# reg_smd_v-1-0.net
KiCad netlist of a schematic drawn in EAGLE
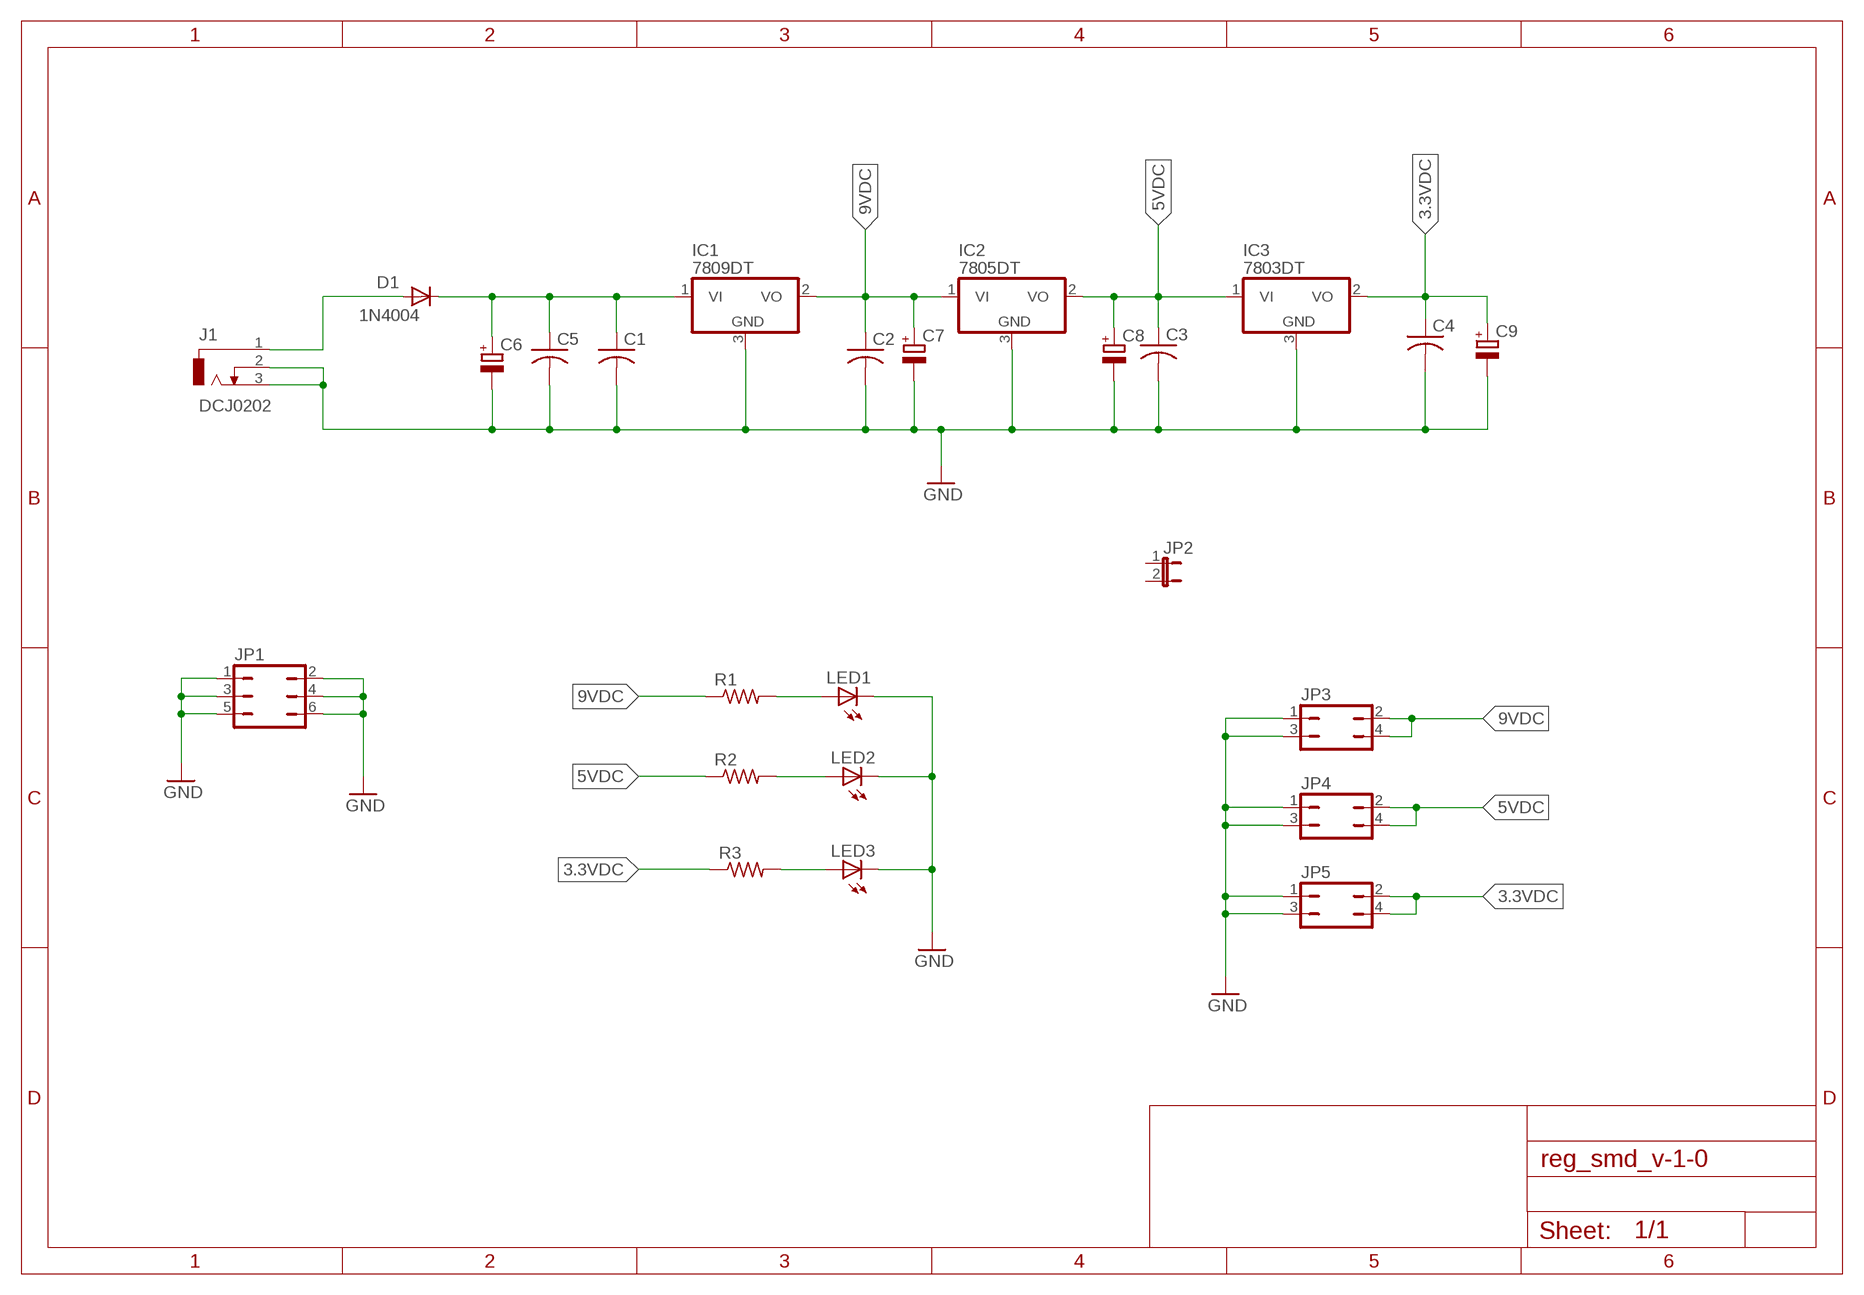
[diagram p0: schematic, sheet 1]

(export (version "E")
  (design (tool "Eeschema 10.0.6"))
  (components
    (comp (ref "C1")
      (value "C-USC1206")
      (footprint "eagle-import:C1206")
      (libsource (lib "eagle-import") (part "C-USC1206"))
    )
    (comp (ref "C2")
      (value "C-USC1206")
      (footprint "eagle-import:C1206")
      (libsource (lib "eagle-import") (part "C-USC1206"))
    )
    (comp (ref "C3")
      (value "C-USC1206")
      (footprint "eagle-import:C1206")
      (libsource (lib "eagle-import") (part "C-USC1206"))
    )
    (comp (ref "C4")
      (value "C-USC1206")
      (footprint "eagle-import:C1206")
      (libsource (lib "eagle-import") (part "C-USC1206"))
    )
    (comp (ref "C5")
      (value "C-USC1206")
      (footprint "eagle-import:C1206")
      (libsource (lib "eagle-import") (part "C-USC1206"))
    )
    (comp (ref "C6")
      (value "CPOL-EUE2.5-6")
      (footprint "eagle-import:E2,5-6")
      (libsource (lib "eagle-import") (part "CPOL-EUE2.5-6"))
    )
    (comp (ref "C7")
      (value "CPOL-EUE2.5-6")
      (footprint "eagle-import:E2,5-6")
      (libsource (lib "eagle-import") (part "CPOL-EUE2.5-6"))
    )
    (comp (ref "C8")
      (value "CPOL-EUE2.5-6")
      (footprint "eagle-import:E2,5-6")
      (libsource (lib "eagle-import") (part "CPOL-EUE2.5-6"))
    )
    (comp (ref "C9")
      (value "CPOL-EUE2.5-6")
      (footprint "eagle-import:E2,5-6")
      (libsource (lib "eagle-import") (part "CPOL-EUE2.5-6"))
    )
    (comp (ref "D1")
      (value "1N4004")
      (footprint "eagle-import:DO41-10")
      (libsource (lib "eagle-import") (part "1N4004"))
    )
    (comp (ref "IC1")
      (value "7809DT")
      (footprint "eagle-import:TO252")
      (libsource (lib "eagle-import") (part "78DT06"))
    )
    (comp (ref "IC2")
      (value "7805DT")
      (footprint "eagle-import:TO252")
      (libsource (lib "eagle-import") (part "78DT06"))
    )
    (comp (ref "IC3")
      (value "7803DT")
      (footprint "eagle-import:TO252")
      (libsource (lib "eagle-import") (part "78DT06"))
    )
    (comp (ref "J1")
      (value "DCJ0202")
      (footprint "eagle-import:DCJ0202")
      (libsource (lib "eagle-import") (part "DCJ0202"))
    )
    (comp (ref "JP1")
      (value "JP3Q")
      (footprint "eagle-import:JP3Q")
      (libsource (lib "eagle-import") (part "JP3Q"))
    )
    (comp (ref "JP2")
      (value "JP1E")
      (footprint "eagle-import:JP1")
      (libsource (lib "eagle-import") (part "JP1E"))
    )
    (comp (ref "JP3")
      (value "JP2Q")
      (footprint "eagle-import:JP2Q")
      (libsource (lib "eagle-import") (part "JP2Q"))
    )
    (comp (ref "JP4")
      (value "JP2Q")
      (footprint "eagle-import:JP2Q")
      (libsource (lib "eagle-import") (part "JP2Q"))
    )
    (comp (ref "JP5")
      (value "JP2Q")
      (footprint "eagle-import:JP2Q")
      (libsource (lib "eagle-import") (part "JP2Q"))
    )
    (comp (ref "LED1")
      (value "LEDCHIPLED_1206")
      (footprint "eagle-import:CHIPLED_1206")
      (libsource (lib "eagle-import") (part "LEDCHIPLED_1206"))
    )
    (comp (ref "LED2")
      (value "LEDCHIPLED_1206")
      (footprint "eagle-import:CHIPLED_1206")
      (libsource (lib "eagle-import") (part "LEDCHIPLED_1206"))
    )
    (comp (ref "LED3")
      (value "LEDCHIPLED_1206")
      (footprint "eagle-import:CHIPLED_1206")
      (libsource (lib "eagle-import") (part "LEDCHIPLED_1206"))
    )
    (comp (ref "R1")
      (value "R-US_M1206")
      (footprint "eagle-import:M1206")
      (libsource (lib "eagle-import") (part "R-US_M1206"))
    )
    (comp (ref "R2")
      (value "R-US_M1206")
      (footprint "eagle-import:M1206")
      (libsource (lib "eagle-import") (part "R-US_M1206"))
    )
    (comp (ref "R3")
      (value "R-US_M1206")
      (footprint "eagle-import:M1206")
      (libsource (lib "eagle-import") (part "R-US_M1206"))
    )
  )
  (nets
    (net (code "1") (name "3.3VDC") (class "Default")
      (node (ref "C4") (pin "1") (pinfunction "1_1") (pintype "passive"))
      (node (ref "C9") (pin "+") (pinfunction "+_+") (pintype "passive"))
      (node (ref "IC3") (pin "2") (pinfunction "VO_2") (pintype "passive"))
      (node (ref "JP5") (pin "2") (pinfunction "2_2") (pintype "passive"))
      (node (ref "JP5") (pin "4") (pinfunction "4_4") (pintype "passive"))
      (node (ref "R3") (pin "1") (pinfunction "1_1") (pintype "passive"))
    )
    (net (code "2") (name "5VDC") (class "Default")
      (node (ref "C3") (pin "1") (pinfunction "1_1") (pintype "passive"))
      (node (ref "C8") (pin "+") (pinfunction "+_+") (pintype "passive"))
      (node (ref "IC2") (pin "2") (pinfunction "VO_2") (pintype "passive"))
      (node (ref "IC3") (pin "1") (pinfunction "VI_1") (pintype "input"))
      (node (ref "JP4") (pin "2") (pinfunction "2_2") (pintype "passive"))
      (node (ref "JP4") (pin "4") (pinfunction "4_4") (pintype "passive"))
      (node (ref "R2") (pin "1") (pinfunction "1_1") (pintype "passive"))
    )
    (net (code "3") (name "9VDC") (class "Default")
      (node (ref "C2") (pin "1") (pinfunction "1_1") (pintype "passive"))
      (node (ref "C7") (pin "+") (pinfunction "+_+") (pintype "passive"))
      (node (ref "IC1") (pin "2") (pinfunction "VO_2") (pintype "passive"))
      (node (ref "IC2") (pin "1") (pinfunction "VI_1") (pintype "input"))
      (node (ref "JP3") (pin "2") (pinfunction "2_2") (pintype "passive"))
      (node (ref "JP3") (pin "4") (pinfunction "4_4") (pintype "passive"))
      (node (ref "R1") (pin "1") (pinfunction "1_1") (pintype "passive"))
    )
    (net (code "4") (name "GND") (class "Default")
      (node (ref "C1") (pin "2") (pinfunction "2_2") (pintype "passive"))
      (node (ref "C2") (pin "2") (pinfunction "2_2") (pintype "passive"))
      (node (ref "C3") (pin "2") (pinfunction "2_2") (pintype "passive"))
      (node (ref "C4") (pin "2") (pinfunction "2_2") (pintype "passive"))
      (node (ref "C5") (pin "2") (pinfunction "2_2") (pintype "passive"))
      (node (ref "C6") (pin "-") (pinfunction "-_-") (pintype "passive"))
      (node (ref "C7") (pin "-") (pinfunction "-_-") (pintype "passive"))
      (node (ref "C8") (pin "-") (pinfunction "-_-") (pintype "passive"))
      (node (ref "C9") (pin "-") (pinfunction "-_-") (pintype "passive"))
      (node (ref "IC1") (pin "3") (pinfunction "GND_3") (pintype "passive"))
      (node (ref "IC2") (pin "3") (pinfunction "GND_3") (pintype "passive"))
      (node (ref "IC3") (pin "3") (pinfunction "GND_3") (pintype "passive"))
      (node (ref "J1") (pin "2") (pinfunction "2_2") (pintype "passive"))
      (node (ref "J1") (pin "3") (pinfunction "3_3") (pintype "passive"))
      (node (ref "JP1") (pin "1") (pinfunction "1_1") (pintype "passive"))
      (node (ref "JP1") (pin "2") (pinfunction "2_2") (pintype "passive"))
      (node (ref "JP1") (pin "3") (pinfunction "3_3") (pintype "passive"))
      (node (ref "JP1") (pin "4") (pinfunction "4_4") (pintype "passive"))
      (node (ref "JP1") (pin "5") (pinfunction "5_5") (pintype "passive"))
      (node (ref "JP1") (pin "6") (pinfunction "6_6") (pintype "passive"))
      (node (ref "JP3") (pin "1") (pinfunction "1_1") (pintype "passive"))
      (node (ref "JP3") (pin "3") (pinfunction "3_3") (pintype "passive"))
      (node (ref "JP4") (pin "1") (pinfunction "1_1") (pintype "passive"))
      (node (ref "JP4") (pin "3") (pinfunction "3_3") (pintype "passive"))
      (node (ref "JP5") (pin "1") (pinfunction "1_1") (pintype "passive"))
      (node (ref "JP5") (pin "3") (pinfunction "3_3") (pintype "passive"))
      (node (ref "LED1") (pin "C") (pinfunction "C_C") (pintype "passive"))
      (node (ref "LED2") (pin "C") (pinfunction "C_C") (pintype "passive"))
      (node (ref "LED3") (pin "C") (pinfunction "C_C") (pintype "passive"))
    )
    (net (code "5") (name "Net-(D1-PadA)") (class "Default")
      (node (ref "D1") (pin "A") (pinfunction "A_A") (pintype "passive"))
      (node (ref "J1") (pin "1") (pinfunction "1_1") (pintype "passive"))
    )
    (net (code "6") (name "Net-(IC1-VI)") (class "Default")
      (node (ref "C1") (pin "1") (pinfunction "1_1") (pintype "passive"))
      (node (ref "C5") (pin "1") (pinfunction "1_1") (pintype "passive"))
      (node (ref "C6") (pin "+") (pinfunction "+_+") (pintype "passive"))
      (node (ref "D1") (pin "C") (pinfunction "C_C") (pintype "passive"))
      (node (ref "IC1") (pin "1") (pinfunction "VI_1") (pintype "input"))
    )
    (net (code "7") (name "Net-(LED1-PadA)") (class "Default")
      (node (ref "LED1") (pin "A") (pinfunction "A_A") (pintype "passive"))
      (node (ref "R1") (pin "2") (pinfunction "2_2") (pintype "passive"))
    )
    (net (code "8") (name "Net-(LED2-PadA)") (class "Default")
      (node (ref "LED2") (pin "A") (pinfunction "A_A") (pintype "passive"))
      (node (ref "R2") (pin "2") (pinfunction "2_2") (pintype "passive"))
    )
    (net (code "9") (name "Net-(LED3-PadA)") (class "Default")
      (node (ref "LED3") (pin "A") (pinfunction "A_A") (pintype "passive"))
      (node (ref "R3") (pin "2") (pinfunction "2_2") (pintype "passive"))
    )
    (net (code "10") (name "unconnected-(JP2-Pad1)") (class "Default")
      (node (ref "JP2") (pin "1") (pinfunction "1_1") (pintype "passive"))
    )
    (net (code "11") (name "unconnected-(JP2-Pad2)") (class "Default")
      (node (ref "JP2") (pin "2") (pinfunction "2_2") (pintype "passive"))
    )
  )
)
